# MAX487_Devboard.net
KiCad netlist of a schematic drawn in EAGLE
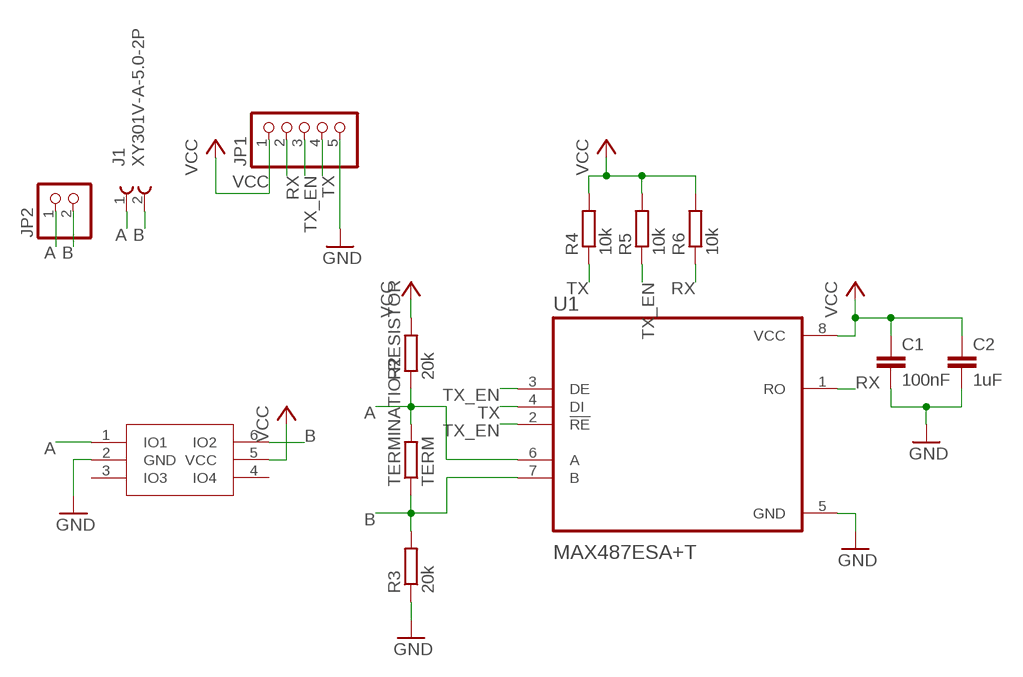
[diagram p0: schematic, sheet 1]

(export (version "E")
  (design (tool "Eeschema 10.0.6"))
  (components
    (comp (ref "C1")
      (value "100nF")
      (footprint "eagle-import:C0603")
      (libsource (lib "eagle-import") (part "C-EUC0603"))
    )
    (comp (ref "C2")
      (value "1uF")
      (footprint "eagle-import:C0603")
      (libsource (lib "eagle-import") (part "C-EUC0603"))
    )
    (comp (ref "J1")
      (value "XY301V-A-5.0-2P")
      (footprint "eagle-import:691102710002")
      (fields (field (name "MF") "Wurth Elektronik") (field (name "MP") "691102710002"))
      (libsource (lib "eagle-import") (part "691102710002"))
    )
    (comp (ref "JP1")
      (value "PINHD-1X5")
      (footprint "eagle-import:1X05")
      (libsource (lib "eagle-import") (part "PINHD-1X5"))
    )
    (comp (ref "JP2")
      (value "PINHD-1X2")
      (footprint "eagle-import:1X02")
      (libsource (lib "eagle-import") (part "PINHD-1X2"))
    )
    (comp (ref "R2")
      (value "20k")
      (footprint "eagle-import:R0402")
      (libsource (lib "eagle-import") (part "R-EU_R0402"))
    )
    (comp (ref "R3")
      (value "20k")
      (footprint "eagle-import:R0402")
      (libsource (lib "eagle-import") (part "R-EU_R0402"))
    )
    (comp (ref "R4")
      (value "10k")
      (footprint "eagle-import:R0402")
      (libsource (lib "eagle-import") (part "R-EU_R0402"))
    )
    (comp (ref "R5")
      (value "10k")
      (footprint "eagle-import:R0402")
      (libsource (lib "eagle-import") (part "R-EU_R0402"))
    )
    (comp (ref "R6")
      (value "10k")
      (footprint "eagle-import:R0402")
      (libsource (lib "eagle-import") (part "R-EU_R0402"))
    )
    (comp (ref "TERMINATIO-RESISTOR")
      (value "TERM")
      (footprint "eagle-import:R0805")
      (libsource (lib "eagle-import") (part "R-EU_R0805"))
    )
    (comp (ref "U1")
      (value "MAX487ESA+T")
      (footprint "eagle-import:SOIC127P600X175-8N")
      (fields (field (name "MF") "Maxim Integrated"))
      (libsource (lib "eagle-import") (part "MAX487ESA+T"))
    )
    (comp (ref "U2")
      (value "ESDU5V0H4")
      (footprint "eagle-import:SOT-23-6")
      (libsource (lib "eagle-import") (part "ESDU5V0H4"))
    )
  )
  (nets
    (net (code "1") (name "/A") (class "Default")
      (node (ref "J1") (pin "1") (pinfunction "1_1") (pintype "passive"))
      (node (ref "JP2") (pin "1") (pinfunction "1_1") (pintype "passive"))
      (node (ref "R2") (pin "1") (pinfunction "1_1") (pintype "passive"))
      (node (ref "TERMINATIO-RESISTOR") (pin "2") (pinfunction "2_2") (pintype "passive"))
      (node (ref "U1") (pin "6") (pinfunction "A_6") (pintype "bidirectional"))
      (node (ref "U2") (pin "1") (pinfunction "IO1_1") (pintype "bidirectional"))
    )
    (net (code "2") (name "/B") (class "Default")
      (node (ref "J1") (pin "2") (pinfunction "2_2") (pintype "passive"))
      (node (ref "JP2") (pin "2") (pinfunction "2_2") (pintype "passive"))
      (node (ref "R3") (pin "2") (pinfunction "2_2") (pintype "passive"))
      (node (ref "TERMINATIO-RESISTOR") (pin "1") (pinfunction "1_1") (pintype "passive"))
      (node (ref "U1") (pin "7") (pinfunction "B_7") (pintype "bidirectional"))
      (node (ref "U2") (pin "6") (pinfunction "IO2_6") (pintype "bidirectional"))
    )
    (net (code "3") (name "/RX") (class "Default")
      (node (ref "JP1") (pin "2") (pinfunction "2_2") (pintype "passive"))
      (node (ref "R6") (pin "1") (pinfunction "1_1") (pintype "passive"))
      (node (ref "U1") (pin "1") (pinfunction "RO_1") (pintype "output"))
    )
    (net (code "4") (name "/TX") (class "Default")
      (node (ref "JP1") (pin "4") (pinfunction "4_4") (pintype "passive"))
      (node (ref "R4") (pin "1") (pinfunction "1_1") (pintype "passive"))
      (node (ref "U1") (pin "4") (pinfunction "DI_4") (pintype "input"))
    )
    (net (code "5") (name "/TX_EN") (class "Default")
      (node (ref "JP1") (pin "3") (pinfunction "3_3") (pintype "passive"))
      (node (ref "R5") (pin "1") (pinfunction "1_1") (pintype "passive"))
      (node (ref "U1") (pin "2") (pinfunction "~{RE}_2") (pintype "input"))
      (node (ref "U1") (pin "3") (pinfunction "DE_3") (pintype "input"))
    )
    (net (code "6") (name "GND") (class "Default")
      (node (ref "C1") (pin "2") (pinfunction "2_2") (pintype "passive"))
      (node (ref "C2") (pin "2") (pinfunction "2_2") (pintype "passive"))
      (node (ref "JP1") (pin "5") (pinfunction "5_5") (pintype "passive"))
      (node (ref "R3") (pin "1") (pinfunction "1_1") (pintype "passive"))
      (node (ref "U1") (pin "5") (pinfunction "GND_5") (pintype "power_in"))
      (node (ref "U2") (pin "2") (pinfunction "GND_2") (pintype "bidirectional"))
    )
    (net (code "7") (name "VCC") (class "Default")
      (node (ref "C1") (pin "1") (pinfunction "1_1") (pintype "passive"))
      (node (ref "C2") (pin "1") (pinfunction "1_1") (pintype "passive"))
      (node (ref "JP1") (pin "1") (pinfunction "1_1") (pintype "passive"))
      (node (ref "R2") (pin "2") (pinfunction "2_2") (pintype "passive"))
      (node (ref "R4") (pin "2") (pinfunction "2_2") (pintype "passive"))
      (node (ref "R5") (pin "2") (pinfunction "2_2") (pintype "passive"))
      (node (ref "R6") (pin "2") (pinfunction "2_2") (pintype "passive"))
      (node (ref "U1") (pin "8") (pinfunction "VCC_8") (pintype "power_in"))
      (node (ref "U2") (pin "5") (pinfunction "VCC_5") (pintype "bidirectional"))
    )
    (net (code "8") (name "unconnected-(U2-IO3-Pad3)") (class "Default")
      (node (ref "U2") (pin "3") (pinfunction "IO3_3") (pintype "bidirectional"))
    )
    (net (code "9") (name "unconnected-(U2-IO4-Pad4)") (class "Default")
      (node (ref "U2") (pin "4") (pinfunction "IO4_4") (pintype "bidirectional"))
    )
  )
)
